# daisyboard.net
KiCad netlist of a schematic drawn in EAGLE
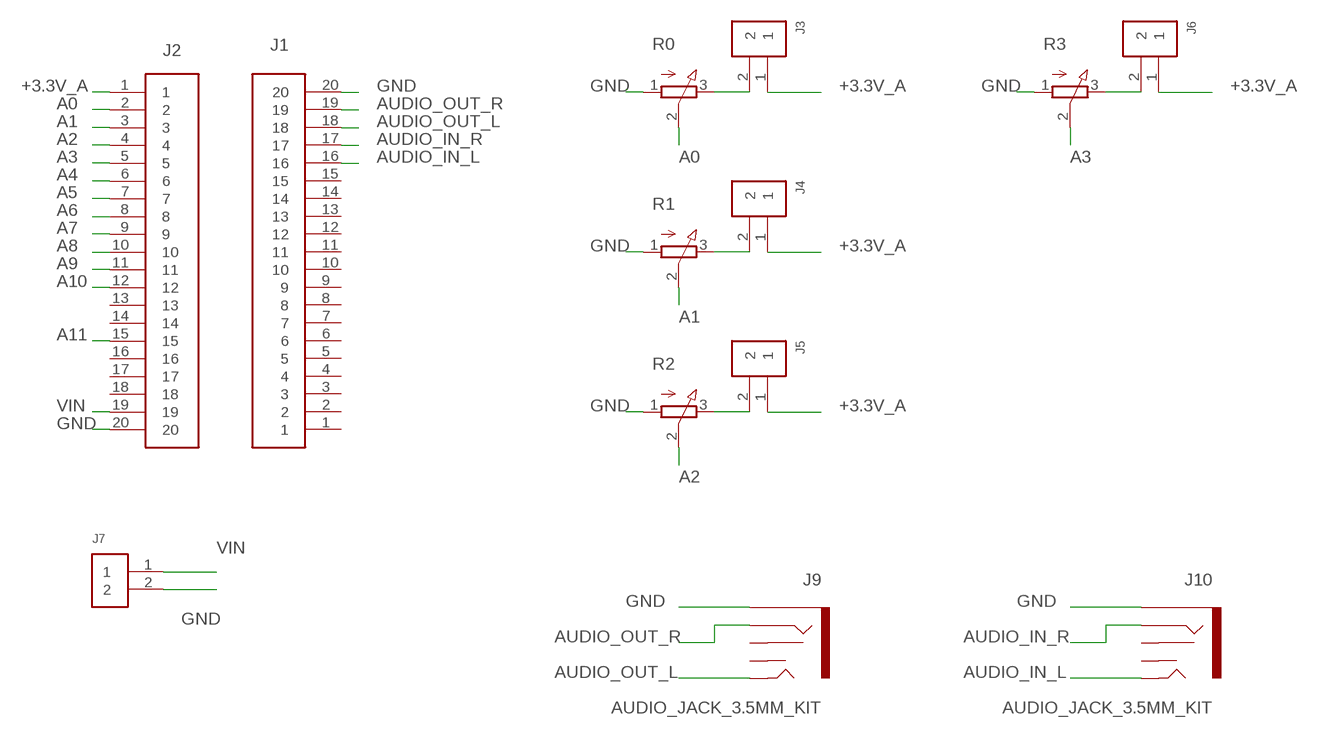
[diagram p0: schematic, sheet 1]

(export (version "E")
  (design (tool "Eeschema 10.0.6"))
  (components
    (comp (ref "J1")
      (value "61302011121")
      (footprint "eagle-import:61302011121")
      (fields
        (field (name "DIGIKEY_PART_NUMBER") "732-5329-ND")
        (field (name "MANUFACTURER") "Wurth Electronics Inc.")
        (field (name "CREATED_BY") "PCBLayout.com")
      )
      (libsource (lib "eagle-import") (part "61302011121"))
    )
    (comp (ref "J2")
      (value "61302011121")
      (footprint "eagle-import:61302011121")
      (fields
        (field (name "DIGIKEY_PART_NUMBER") "732-5329-ND")
        (field (name "MANUFACTURER") "Wurth Electronics Inc.")
        (field (name "CREATED_BY") "PCBLayout.com")
      )
      (libsource (lib "eagle-import") (part "61302011121"))
    )
    (comp (ref "J3")
      (value "61300211121")
      (footprint "eagle-import:61300211121")
      (fields
        (field (name "DIGI_KEY_PART_NUMBER") "732-5315-ND")
        (field (name "MANUFACTURER") "Wurth Electronics Inc.")
        (field (name "CREATED_BY") "PCBLayout.com")
      )
      (libsource (lib "eagle-import") (part "61300211121"))
    )
    (comp (ref "J4")
      (value "61300211121")
      (footprint "eagle-import:61300211121")
      (fields
        (field (name "DIGI_KEY_PART_NUMBER") "732-5315-ND")
        (field (name "MANUFACTURER") "Wurth Electronics Inc.")
        (field (name "CREATED_BY") "PCBLayout.com")
      )
      (libsource (lib "eagle-import") (part "61300211121"))
    )
    (comp (ref "J5")
      (value "61300211121")
      (footprint "eagle-import:61300211121")
      (fields
        (field (name "DIGI_KEY_PART_NUMBER") "732-5315-ND")
        (field (name "MANUFACTURER") "Wurth Electronics Inc.")
        (field (name "CREATED_BY") "PCBLayout.com")
      )
      (libsource (lib "eagle-import") (part "61300211121"))
    )
    (comp (ref "J6")
      (value "61300211121")
      (footprint "eagle-import:61300211121")
      (fields
        (field (name "DIGI_KEY_PART_NUMBER") "732-5315-ND")
        (field (name "MANUFACTURER") "Wurth Electronics Inc.")
        (field (name "CREATED_BY") "PCBLayout.com")
      )
      (libsource (lib "eagle-import") (part "61300211121"))
    )
    (comp (ref "J7")
      (value "61300211121")
      (footprint "eagle-import:61300211121")
      (fields
        (field (name "DIGI_KEY_PART_NUMBER") "732-5315-ND")
        (field (name "MANUFACTURER") "Wurth Electronics Inc.")
        (field (name "CREATED_BY") "PCBLayout.com")
      )
      (libsource (lib "eagle-import") (part "61300211121"))
    )
    (comp (ref "J9")
      (value "AUDIO_JACK_3.5MM_KIT")
      (footprint "eagle-import:AUDIO-JACK-KIT")
      (libsource (lib "eagle-import") (part "AUDIO_JACK_3.5MM_KIT"))
    )
    (comp (ref "J10")
      (value "AUDIO_JACK_3.5MM_KIT")
      (footprint "eagle-import:AUDIO-JACK-KIT")
      (libsource (lib "eagle-import") (part "AUDIO_JACK_3.5MM_KIT"))
    )
    (comp (ref "R0")
      (value "3RP/1610N")
      (footprint "eagle-import:3RP_1610N")
      (libsource (lib "eagle-import") (part "3RP/1610N"))
    )
    (comp (ref "R1")
      (value "3RP/1610N")
      (footprint "eagle-import:3RP_1610N")
      (libsource (lib "eagle-import") (part "3RP/1610N"))
    )
    (comp (ref "R2")
      (value "3RP/1610N")
      (footprint "eagle-import:3RP_1610N")
      (libsource (lib "eagle-import") (part "3RP/1610N"))
    )
    (comp (ref "R3")
      (value "3RP/1610N")
      (footprint "eagle-import:3RP_1610N")
      (libsource (lib "eagle-import") (part "3RP/1610N"))
    )
  )
  (nets
    (net (code "1") (name "/+3.3V_A") (class "Default")
      (node (ref "J2") (pin "1") (pinfunction "1_1") (pintype "passive"))
      (node (ref "J3") (pin "1") (pinfunction "1_1") (pintype "passive"))
      (node (ref "J4") (pin "1") (pinfunction "1_1") (pintype "passive"))
      (node (ref "J5") (pin "1") (pinfunction "1_1") (pintype "passive"))
      (node (ref "J6") (pin "1") (pinfunction "1_1") (pintype "passive"))
    )
    (net (code "2") (name "/A0") (class "Default")
      (node (ref "J2") (pin "2") (pinfunction "2_2") (pintype "passive"))
      (node (ref "R0") (pin "2") (pinfunction "S_2") (pintype "passive"))
    )
    (net (code "3") (name "/A1") (class "Default")
      (node (ref "J2") (pin "3") (pinfunction "3_3") (pintype "passive"))
      (node (ref "R1") (pin "2") (pinfunction "S_2") (pintype "passive"))
    )
    (net (code "4") (name "/A2") (class "Default")
      (node (ref "J2") (pin "4") (pinfunction "4_4") (pintype "passive"))
      (node (ref "R2") (pin "2") (pinfunction "S_2") (pintype "passive"))
    )
    (net (code "5") (name "/A3") (class "Default")
      (node (ref "J2") (pin "5") (pinfunction "5_5") (pintype "passive"))
      (node (ref "R3") (pin "2") (pinfunction "S_2") (pintype "passive"))
    )
    (net (code "6") (name "/A4") (class "Default")
      (node (ref "J2") (pin "6") (pinfunction "6_6") (pintype "passive"))
    )
    (net (code "7") (name "/A5") (class "Default")
      (node (ref "J2") (pin "7") (pinfunction "7_7") (pintype "passive"))
    )
    (net (code "8") (name "/A6") (class "Default")
      (node (ref "J2") (pin "8") (pinfunction "8_8") (pintype "passive"))
    )
    (net (code "9") (name "/A7") (class "Default")
      (node (ref "J2") (pin "9") (pinfunction "9_9") (pintype "passive"))
    )
    (net (code "10") (name "/A8") (class "Default")
      (node (ref "J2") (pin "10") (pinfunction "10_10") (pintype "passive"))
    )
    (net (code "11") (name "/A9") (class "Default")
      (node (ref "J2") (pin "11") (pinfunction "11_11") (pintype "passive"))
    )
    (net (code "12") (name "/A10") (class "Default")
      (node (ref "J2") (pin "12") (pinfunction "12_12") (pintype "passive"))
    )
    (net (code "13") (name "/A11") (class "Default")
      (node (ref "J2") (pin "15") (pinfunction "15_15") (pintype "passive"))
    )
    (net (code "14") (name "/AUDIO_IN_L") (class "Default")
      (node (ref "J1") (pin "16") (pinfunction "16_16") (pintype "passive"))
      (node (ref "J10") (pin "TIP") (pinfunction "TIP_TIP") (pintype "bidirectional"))
    )
    (net (code "15") (name "/AUDIO_IN_R") (class "Default")
      (node (ref "J1") (pin "17") (pinfunction "17_17") (pintype "passive"))
      (node (ref "J10") (pin "RING") (pinfunction "RING_RING") (pintype "bidirectional"))
    )
    (net (code "16") (name "/AUDIO_OUT_L") (class "Default")
      (node (ref "J1") (pin "18") (pinfunction "18_18") (pintype "passive"))
      (node (ref "J9") (pin "TIP") (pinfunction "TIP_TIP") (pintype "bidirectional"))
    )
    (net (code "17") (name "/AUDIO_OUT_R") (class "Default")
      (node (ref "J1") (pin "19") (pinfunction "19_19") (pintype "passive"))
      (node (ref "J9") (pin "RING") (pinfunction "RING_RING") (pintype "bidirectional"))
    )
    (net (code "18") (name "/GND") (class "Default")
      (node (ref "J1") (pin "20") (pinfunction "20_20") (pintype "passive"))
      (node (ref "J10") (pin "SLEEVE") (pinfunction "SLEEVE_SLEEVE") (pintype "bidirectional"))
      (node (ref "J2") (pin "20") (pinfunction "20_20") (pintype "passive"))
      (node (ref "J7") (pin "2") (pinfunction "2_2") (pintype "passive"))
      (node (ref "J9") (pin "SLEEVE") (pinfunction "SLEEVE_SLEEVE") (pintype "bidirectional"))
      (node (ref "R0") (pin "1") (pinfunction "A_1") (pintype "passive"))
      (node (ref "R1") (pin "1") (pinfunction "A_1") (pintype "passive"))
      (node (ref "R2") (pin "1") (pinfunction "A_1") (pintype "passive"))
      (node (ref "R3") (pin "1") (pinfunction "A_1") (pintype "passive"))
    )
    (net (code "19") (name "/VIN") (class "Default")
      (node (ref "J2") (pin "19") (pinfunction "19_19") (pintype "passive"))
      (node (ref "J7") (pin "1") (pinfunction "1_1") (pintype "passive"))
    )
    (net (code "20") (name "Net-(R0-E)") (class "Default")
      (node (ref "J3") (pin "2") (pinfunction "2_2") (pintype "passive"))
      (node (ref "R0") (pin "3") (pinfunction "E_3") (pintype "passive"))
    )
    (net (code "21") (name "Net-(R1-E)") (class "Default")
      (node (ref "J4") (pin "2") (pinfunction "2_2") (pintype "passive"))
      (node (ref "R1") (pin "3") (pinfunction "E_3") (pintype "passive"))
    )
    (net (code "22") (name "Net-(R2-E)") (class "Default")
      (node (ref "J5") (pin "2") (pinfunction "2_2") (pintype "passive"))
      (node (ref "R2") (pin "3") (pinfunction "E_3") (pintype "passive"))
    )
    (net (code "23") (name "Net-(R3-E)") (class "Default")
      (node (ref "J6") (pin "2") (pinfunction "2_2") (pintype "passive"))
      (node (ref "R3") (pin "3") (pinfunction "E_3") (pintype "passive"))
    )
    (net (code "24") (name "unconnected-(J1-Pad1)") (class "Default")
      (node (ref "J1") (pin "1") (pinfunction "1_1") (pintype "passive"))
    )
    (net (code "25") (name "unconnected-(J1-Pad2)") (class "Default")
      (node (ref "J1") (pin "2") (pinfunction "2_2") (pintype "passive"))
    )
    (net (code "26") (name "unconnected-(J1-Pad3)") (class "Default")
      (node (ref "J1") (pin "3") (pinfunction "3_3") (pintype "passive"))
    )
    (net (code "27") (name "unconnected-(J1-Pad4)") (class "Default")
      (node (ref "J1") (pin "4") (pinfunction "4_4") (pintype "passive"))
    )
    (net (code "28") (name "unconnected-(J1-Pad5)") (class "Default")
      (node (ref "J1") (pin "5") (pinfunction "5_5") (pintype "passive"))
    )
    (net (code "29") (name "unconnected-(J1-Pad6)") (class "Default")
      (node (ref "J1") (pin "6") (pinfunction "6_6") (pintype "passive"))
    )
    (net (code "30") (name "unconnected-(J1-Pad7)") (class "Default")
      (node (ref "J1") (pin "7") (pinfunction "7_7") (pintype "passive"))
    )
    (net (code "31") (name "unconnected-(J1-Pad8)") (class "Default")
      (node (ref "J1") (pin "8") (pinfunction "8_8") (pintype "passive"))
    )
    (net (code "32") (name "unconnected-(J1-Pad9)") (class "Default")
      (node (ref "J1") (pin "9") (pinfunction "9_9") (pintype "passive"))
    )
    (net (code "33") (name "unconnected-(J1-Pad10)") (class "Default")
      (node (ref "J1") (pin "10") (pinfunction "10_10") (pintype "passive"))
    )
    (net (code "34") (name "unconnected-(J1-Pad11)") (class "Default")
      (node (ref "J1") (pin "11") (pinfunction "11_11") (pintype "passive"))
    )
    (net (code "35") (name "unconnected-(J1-Pad12)") (class "Default")
      (node (ref "J1") (pin "12") (pinfunction "12_12") (pintype "passive"))
    )
    (net (code "36") (name "unconnected-(J1-Pad13)") (class "Default")
      (node (ref "J1") (pin "13") (pinfunction "13_13") (pintype "passive"))
    )
    (net (code "37") (name "unconnected-(J1-Pad14)") (class "Default")
      (node (ref "J1") (pin "14") (pinfunction "14_14") (pintype "passive"))
    )
    (net (code "38") (name "unconnected-(J1-Pad15)") (class "Default")
      (node (ref "J1") (pin "15") (pinfunction "15_15") (pintype "passive"))
    )
    (net (code "39") (name "unconnected-(J2-Pad13)") (class "Default")
      (node (ref "J2") (pin "13") (pinfunction "13_13") (pintype "passive"))
    )
    (net (code "40") (name "unconnected-(J2-Pad14)") (class "Default")
      (node (ref "J2") (pin "14") (pinfunction "14_14") (pintype "passive"))
    )
    (net (code "41") (name "unconnected-(J2-Pad16)") (class "Default")
      (node (ref "J2") (pin "16") (pinfunction "16_16") (pintype "passive"))
    )
    (net (code "42") (name "unconnected-(J2-Pad17)") (class "Default")
      (node (ref "J2") (pin "17") (pinfunction "17_17") (pintype "passive"))
    )
    (net (code "43") (name "unconnected-(J2-Pad18)") (class "Default")
      (node (ref "J2") (pin "18") (pinfunction "18_18") (pintype "passive"))
    )
    (net (code "44") (name "unconnected-(J9-PadRSH)") (class "Default")
      (node (ref "J9") (pin "RSH") (pinfunction "RSH_RSH") (pintype "bidirectional"))
    )
    (net (code "45") (name "unconnected-(J9-PadTSH)") (class "Default")
      (node (ref "J9") (pin "TSH") (pinfunction "TSH_TSH") (pintype "bidirectional"))
    )
    (net (code "46") (name "unconnected-(J10-PadRSH)") (class "Default")
      (node (ref "J10") (pin "RSH") (pinfunction "RSH_RSH") (pintype "bidirectional"))
    )
    (net (code "47") (name "unconnected-(J10-PadTSH)") (class "Default")
      (node (ref "J10") (pin "TSH") (pinfunction "TSH_TSH") (pintype "bidirectional"))
    )
  )
)
